# Addon-mapleCUx_Raspi-3V3-UART-CC2530-V03.net
KiCad netlist of a schematic drawn in EAGLE
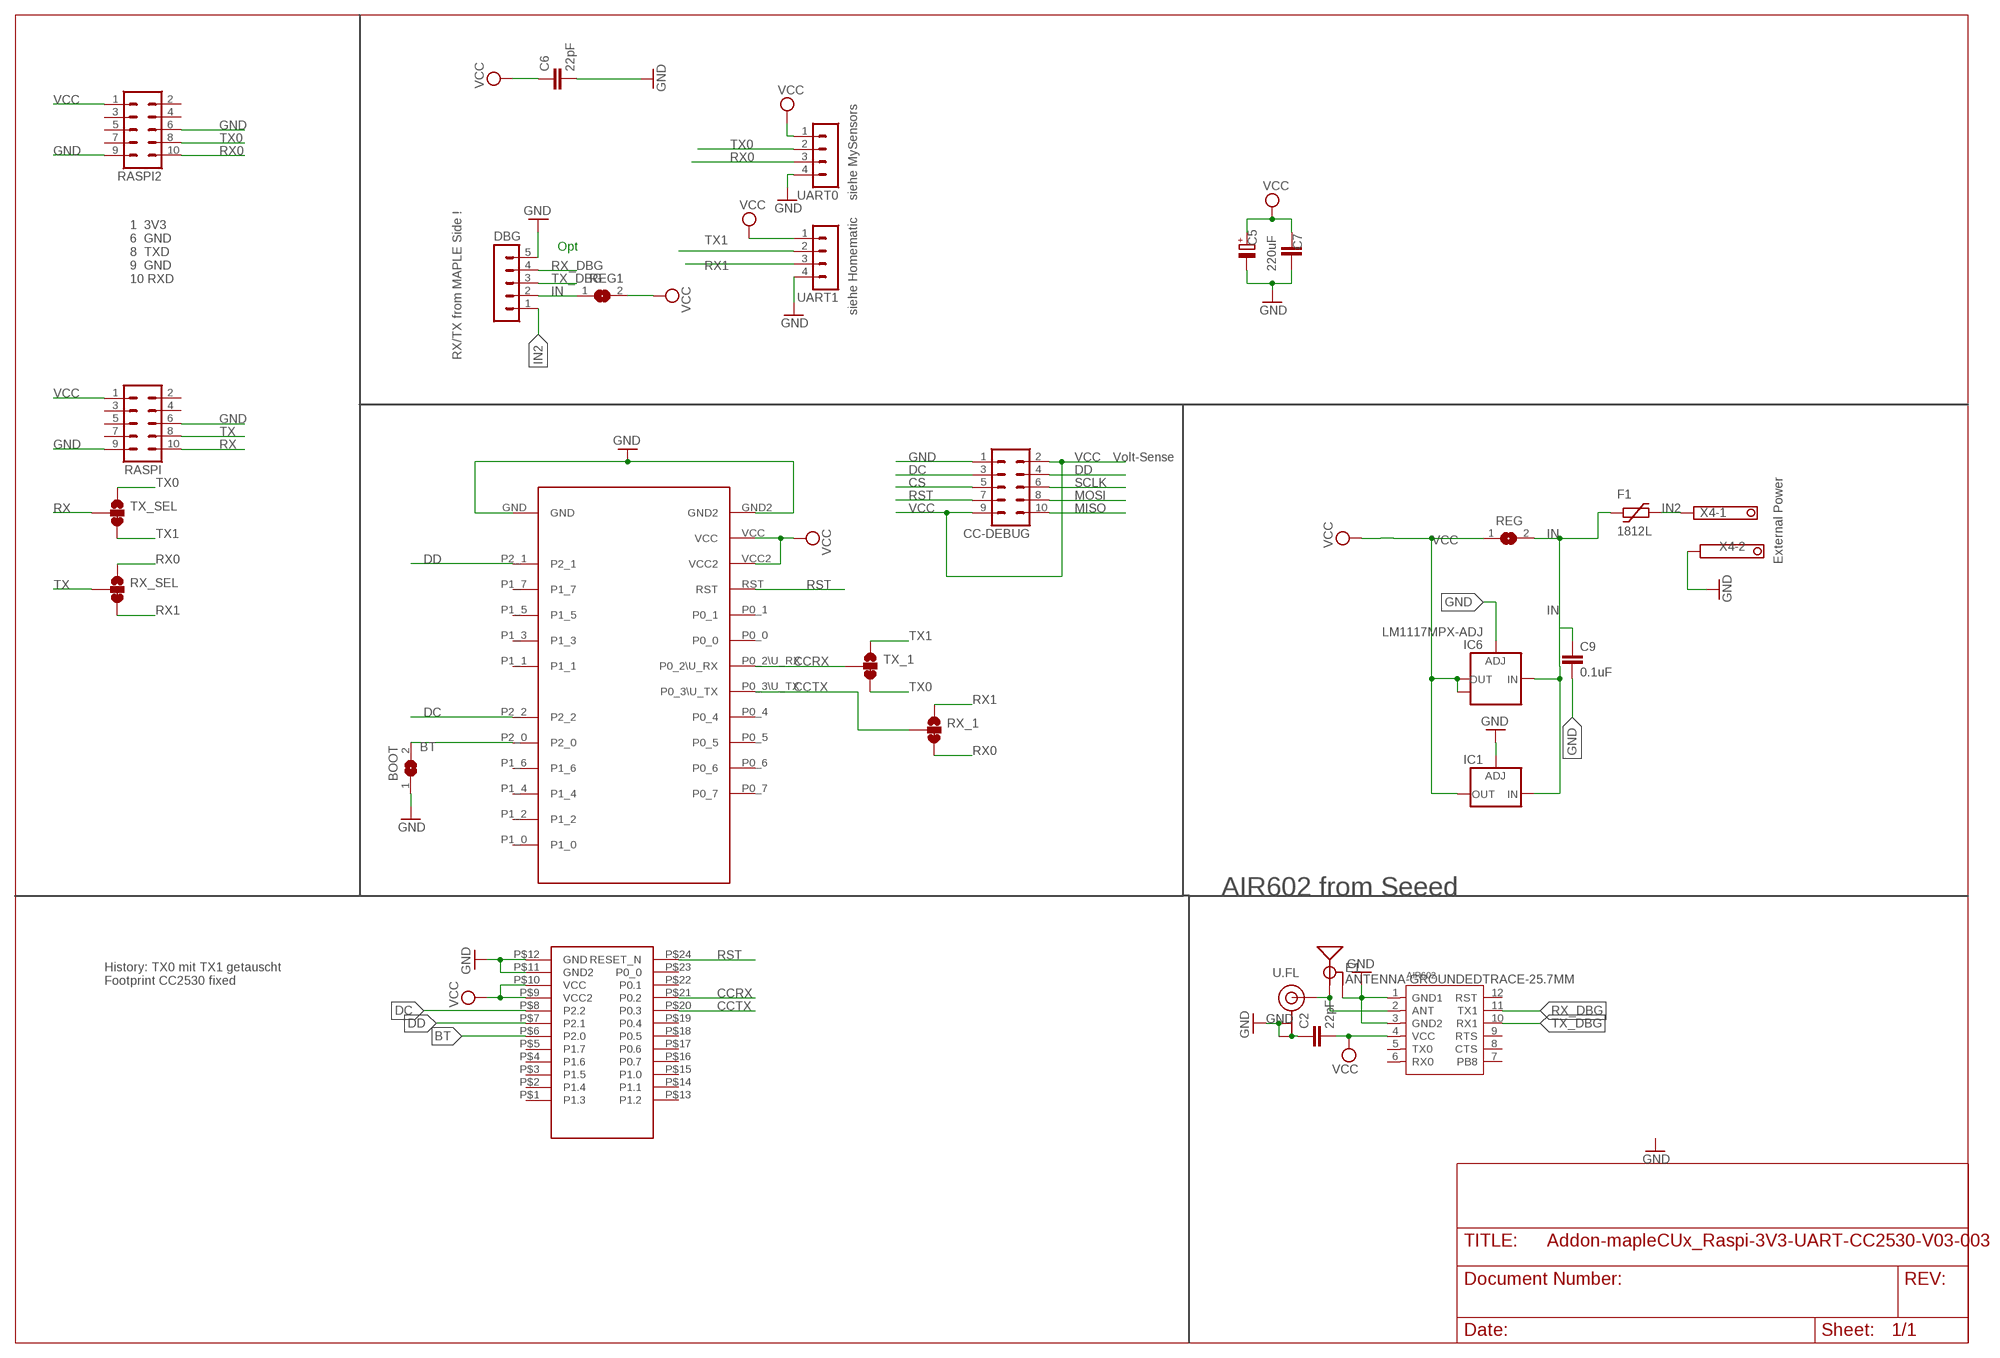
[diagram p0: schematic, sheet 1]

(export (version "E")
  (design (tool "Eeschema 10.0.6"))
  (components
    (comp (ref "AIR602")
      (value "AIR602")
      (footprint "eagle-import:MODULE12P-2.0-10X12MM")
      (libsource (lib "eagle-import") (part "AIR602"))
    )
    (comp (ref "BOOT")
      (value "SJ")
      (footprint "eagle-import:SJ")
      (libsource (lib "eagle-import") (part "SJ"))
    )
    (comp (ref "C2")
      (value "22pF")
      (footprint "eagle-import:C0805")
      (libsource (lib "eagle-import") (part "C-EUC0805"))
    )
    (comp (ref "C5")
      (value "220uF")
      (footprint "eagle-import:E5-8,5")
      (libsource (lib "eagle-import") (part "CPOL-EUE5-8.5"))
    )
    (comp (ref "C6")
      (value "22pF")
      (footprint "eagle-import:C0805")
      (libsource (lib "eagle-import") (part "rcl_334_C-EUC0805"))
    )
    (comp (ref "C7")
      (value "C-EUC1812")
      (footprint "eagle-import:C1812")
      (libsource (lib "eagle-import") (part "rcl_334_C-EUC1812"))
    )
    (comp (ref "C9")
      (value "0.1uF")
      (footprint "eagle-import:C1206")
      (libsource (lib "eagle-import") (part "rcl_334_C-EUC1206"))
    )
    (comp (ref "CC-DEBUG")
      (value "MA05-2")
      (footprint "eagle-import:MA05-2")
      (libsource (lib "eagle-import") (part "MA05-2"))
    )
    (comp (ref "DBG")
      (value "MA05-1")
      (footprint "eagle-import:MA05-1")
      (libsource (lib "eagle-import") (part "MA05-1"))
    )
    (comp (ref "E1")
      (value "ANTENNA-GROUNDEDTRACE-25.7MM")
      (footprint "eagle-import:TRACE_ANTENNA_2.4GHZ_25.7MM")
      (libsource (lib "eagle-import") (part "ANTENNA-GROUNDEDTRACE-25.7MM"))
    )
    (comp (ref "F1")
      (value "1812L")
      (footprint "eagle-import:1812L")
      (libsource (lib "eagle-import") (part "1812L"))
    )
    (comp (ref "IC1")
      (value "LD117ADT50TR")
      (footprint "eagle-import:DPACK")
      (libsource (lib "eagle-import") (part "LD117A?DT50TR"))
    )
    (comp (ref "IC6")
      (value "LM1117MPX-ADJ")
      (footprint "eagle-import:SOT223")
      (libsource (lib "eagle-import") (part "LM1117MPX-ADJ"))
    )
    (comp (ref "RASPI")
      (value "MA05-2")
      (footprint "eagle-import:MA05-2")
      (libsource (lib "eagle-import") (part "MA05-2"))
    )
    (comp (ref "RASPI2")
      (value "MA05-2")
      (footprint "eagle-import:MA05-2")
      (libsource (lib "eagle-import") (part "MA05-2"))
    )
    (comp (ref "REG") (value "SJ") (footprint "eagle-import:SJ") (libsource (lib "eagle-import") (part "SJ")))
    (comp (ref "REG1")
      (value "SJ")
      (footprint "eagle-import:SJ")
      (libsource (lib "eagle-import") (part "SJ"))
    )
    (comp (ref "RX_1")
      (value "JUMPER-SMT_3_1-NC_TRACE_SILK")
      (footprint "eagle-import:SMT-JUMPER_3_1-NC_TRACE_SILK")
      (libsource (lib "eagle-import") (part "JUMPER-SMT_3_1-NC_TRACE_SILK"))
    )
    (comp (ref "RX_SEL")
      (value "JUMPER-SMT_3_1-NC_TRACE_SILK")
      (footprint "eagle-import:SMT-JUMPER_3_1-NC_TRACE_SILK")
      (libsource (lib "eagle-import") (part "JUMPER-SMT_3_1-NC_TRACE_SILK"))
    )
    (comp (ref "TX_1")
      (value "JUMPER-SMT_3_1-NC_TRACE_SILK")
      (footprint "eagle-import:SMT-JUMPER_3_1-NC_TRACE_SILK")
      (libsource (lib "eagle-import") (part "JUMPER-SMT_3_1-NC_TRACE_SILK"))
    )
    (comp (ref "TX_SEL")
      (value "JUMPER-SMT_3_1-NC_TRACE_SILK")
      (footprint "eagle-import:SMT-JUMPER_3_1-NC_TRACE_SILK")
      (libsource (lib "eagle-import") (part "JUMPER-SMT_3_1-NC_TRACE_SILK"))
    )
    (comp (ref "U$1")
      (value "CC2530CC2530PA")
      (footprint "eagle-import:CC2530PA")
      (libsource (lib "eagle-import") (part "CC2530CC2530PA"))
    )
    (comp (ref "U$3")
      (value "CC2530_MODULE")
      (footprint "eagle-import:CC2530_DIL")
      (libsource (lib "eagle-import") (part "CC2530_MODULE"))
    )
    (comp (ref "U.FL")
      (value "U.FL")
      (footprint "eagle-import:U.FL")
      (libsource (lib "eagle-import") (part "U.FL"))
    )
    (comp (ref "UART0")
      (value "MA04-1")
      (footprint "eagle-import:MA04-1")
      (libsource (lib "eagle-import") (part "MA04-1"))
    )
    (comp (ref "UART1")
      (value "MA04-1")
      (footprint "eagle-import:MA04-1")
      (libsource (lib "eagle-import") (part "MA04-1"))
    )
    (comp (ref "X4")
      (value "1751248")
      (footprint "eagle-import:1751248")
      (libsource (lib "eagle-import") (part "1751248"))
    )
  )
  (nets
    (net (code "1") (name "/CCRX") (class "Default")
      (node (ref "TX_1") (pin "2") (pinfunction "2_2") (pintype "passive"))
      (node (ref "U$1") (pin "P$21") (pinfunction "P0.2_P$21") (pintype "bidirectional"))
      (node (ref "U$3") (pin "P0_2\\U_RX") (pinfunction "P0_2\\U_RX_P0_2\\U_RX") (pintype "bidirectional"))
    )
    (net (code "2") (name "/CCTX") (class "Default")
      (node (ref "RX_1") (pin "2") (pinfunction "2_2") (pintype "passive"))
      (node (ref "U$1") (pin "P$20") (pinfunction "P0.3_P$20") (pintype "bidirectional"))
      (node (ref "U$3") (pin "P0_3\\U_TX") (pinfunction "P0_3\\U_TX_P0_3\\U_TX") (pintype "bidirectional"))
    )
    (net (code "3") (name "/CS") (class "Default")
      (node (ref "CC-DEBUG") (pin "5") (pinfunction "5_5") (pintype "passive"))
    )
    (net (code "4") (name "/IN") (class "Default")
      (node (ref "C9") (pin "1") (pinfunction "1_1") (pintype "passive"))
      (node (ref "DBG") (pin "2") (pinfunction "2_2") (pintype "passive"))
      (node (ref "F1") (pin "P$1") (pinfunction "1_P$1") (pintype "passive"))
      (node (ref "IC1") (pin "3") (pinfunction "IN_3") (pintype "input"))
      (node (ref "IC6") (pin "3") (pinfunction "IN_3") (pintype "input"))
      (node (ref "REG") (pin "2") (pinfunction "2_2") (pintype "passive"))
      (node (ref "REG1") (pin "1") (pinfunction "1_1") (pintype "passive"))
    )
    (net (code "5") (name "/MISO") (class "Default")
      (node (ref "CC-DEBUG") (pin "10") (pinfunction "10_10") (pintype "passive"))
    )
    (net (code "6") (name "/MOSI") (class "Default")
      (node (ref "CC-DEBUG") (pin "8") (pinfunction "8_8") (pintype "passive"))
    )
    (net (code "7") (name "/RST") (class "Default")
      (node (ref "CC-DEBUG") (pin "7") (pinfunction "7_7") (pintype "passive"))
      (node (ref "U$1") (pin "P$24") (pinfunction "RESET_N_P$24") (pintype "bidirectional"))
      (node (ref "U$3") (pin "RST") (pinfunction "RST_RST") (pintype "bidirectional"))
    )
    (net (code "8") (name "/RX") (class "Default")
      (node (ref "RASPI") (pin "10") (pinfunction "10_10") (pintype "passive"))
      (node (ref "TX_SEL") (pin "2") (pinfunction "2_2") (pintype "passive"))
    )
    (net (code "9") (name "/RX0") (class "Default")
      (node (ref "RASPI2") (pin "10") (pinfunction "10_10") (pintype "passive"))
      (node (ref "RX_1") (pin "3") (pinfunction "3_3") (pintype "passive"))
      (node (ref "RX_SEL") (pin "1") (pinfunction "1_1") (pintype "passive"))
      (node (ref "UART0") (pin "3") (pinfunction "3_3") (pintype "passive"))
    )
    (net (code "10") (name "/RX1") (class "Default")
      (node (ref "RX_1") (pin "1") (pinfunction "1_1") (pintype "passive"))
      (node (ref "RX_SEL") (pin "3") (pinfunction "3_3") (pintype "passive"))
      (node (ref "UART1") (pin "3") (pinfunction "3_3") (pintype "passive"))
    )
    (net (code "11") (name "/SCLK") (class "Default")
      (node (ref "CC-DEBUG") (pin "6") (pinfunction "6_6") (pintype "passive"))
    )
    (net (code "12") (name "/TX") (class "Default")
      (node (ref "RASPI") (pin "8") (pinfunction "8_8") (pintype "passive"))
      (node (ref "RX_SEL") (pin "2") (pinfunction "2_2") (pintype "passive"))
    )
    (net (code "13") (name "/TX0") (class "Default")
      (node (ref "RASPI2") (pin "8") (pinfunction "8_8") (pintype "passive"))
      (node (ref "TX_1") (pin "3") (pinfunction "3_3") (pintype "passive"))
      (node (ref "TX_SEL") (pin "1") (pinfunction "1_1") (pintype "passive"))
      (node (ref "UART0") (pin "2") (pinfunction "2_2") (pintype "passive"))
    )
    (net (code "14") (name "/TX1") (class "Default")
      (node (ref "TX_1") (pin "1") (pinfunction "1_1") (pintype "passive"))
      (node (ref "TX_SEL") (pin "3") (pinfunction "3_3") (pintype "passive"))
      (node (ref "UART1") (pin "2") (pinfunction "2_2") (pintype "passive"))
    )
    (net (code "15") (name "BT") (class "Default")
      (node (ref "BOOT") (pin "2") (pinfunction "2_2") (pintype "passive"))
      (node (ref "U$1") (pin "P$6") (pinfunction "P2.0_P$6") (pintype "bidirectional"))
      (node (ref "U$3") (pin "P2_0") (pinfunction "P2_0_P2_0") (pintype "bidirectional"))
    )
    (net (code "16") (name "DC") (class "Default")
      (node (ref "CC-DEBUG") (pin "3") (pinfunction "3_3") (pintype "passive"))
      (node (ref "U$1") (pin "P$8") (pinfunction "P2.2_P$8") (pintype "bidirectional"))
      (node (ref "U$3") (pin "P2_2") (pinfunction "P2_2_P2_2") (pintype "bidirectional"))
    )
    (net (code "17") (name "DD") (class "Default")
      (node (ref "CC-DEBUG") (pin "4") (pinfunction "4_4") (pintype "passive"))
      (node (ref "U$1") (pin "P$7") (pinfunction "P2.1_P$7") (pintype "bidirectional"))
      (node (ref "U$3") (pin "P2_1") (pinfunction "P2_1_P2_1") (pintype "bidirectional"))
    )
    (net (code "18") (name "GND") (class "Default")
      (node (ref "AIR602") (pin "1") (pinfunction "GND1_1") (pintype "bidirectional"))
      (node (ref "AIR602") (pin "3") (pinfunction "GND2_3") (pintype "bidirectional"))
      (node (ref "BOOT") (pin "1") (pinfunction "1_1") (pintype "passive"))
      (node (ref "C2") (pin "1") (pinfunction "1_1") (pintype "passive"))
      (node (ref "C5") (pin "-") (pinfunction "-_-") (pintype "passive"))
      (node (ref "C6") (pin "2") (pinfunction "2_2") (pintype "passive"))
      (node (ref "C7") (pin "1") (pinfunction "1_1") (pintype "passive"))
      (node (ref "C9") (pin "2") (pinfunction "2_2") (pintype "passive"))
      (node (ref "CC-DEBUG") (pin "1") (pinfunction "1_1") (pintype "passive"))
      (node (ref "DBG") (pin "5") (pinfunction "5_5") (pintype "passive"))
      (node (ref "E1") (pin "GND") (pinfunction "GND_GND") (pintype "bidirectional"))
      (node (ref "E1") (pin "GND2") (pinfunction "GND_GND2") (pintype "bidirectional"))
      (node (ref "IC1") (pin "1") (pinfunction "ADJ_1") (pintype "input"))
      (node (ref "IC6") (pin "1") (pinfunction "ADJ_1") (pintype "input"))
      (node (ref "RASPI") (pin "6") (pinfunction "6_6") (pintype "passive"))
      (node (ref "RASPI") (pin "9") (pinfunction "9_9") (pintype "passive"))
      (node (ref "RASPI2") (pin "6") (pinfunction "6_6") (pintype "passive"))
      (node (ref "RASPI2") (pin "9") (pinfunction "9_9") (pintype "passive"))
      (node (ref "U$1") (pin "P$11") (pinfunction "GND2_P$11") (pintype "bidirectional"))
      (node (ref "U$1") (pin "P$12") (pinfunction "GND_P$12") (pintype "bidirectional"))
      (node (ref "U$3") (pin "GND") (pinfunction "GND_GND") (pintype "bidirectional"))
      (node (ref "U$3") (pin "GND2") (pinfunction "GND2_GND2") (pintype "bidirectional"))
      (node (ref "U.FL") (pin "1") (pinfunction "GND_1") (pintype "bidirectional"))
      (node (ref "U.FL") (pin "2") (pinfunction "GND_2") (pintype "bidirectional"))
      (node (ref "UART0") (pin "4") (pinfunction "4_4") (pintype "passive"))
      (node (ref "UART1") (pin "4") (pinfunction "4_4") (pintype "passive"))
      (node (ref "X4") (pin "2") (pinfunction "K_2") (pintype "passive"))
    )
    (net (code "19") (name "IN2") (class "Default")
      (node (ref "DBG") (pin "1") (pinfunction "1_1") (pintype "passive"))
      (node (ref "F1") (pin "P$2") (pinfunction "2_P$2") (pintype "passive"))
      (node (ref "X4") (pin "1") (pinfunction "K_1") (pintype "passive"))
    )
    (net (code "20") (name "Net-(AIR602-ANT)") (class "Default")
      (node (ref "AIR602") (pin "2") (pinfunction "ANT_2") (pintype "bidirectional"))
      (node (ref "E1") (pin "ANT") (pinfunction "SIGNAL_ANT") (pintype "bidirectional"))
      (node (ref "U.FL") (pin "FEED") (pinfunction "SIGNAL_FEED") (pintype "bidirectional"))
    )
    (net (code "21") (name "RX_DBG") (class "Default")
      (node (ref "AIR602") (pin "11") (pinfunction "TX1_11") (pintype "bidirectional"))
      (node (ref "DBG") (pin "4") (pinfunction "4_4") (pintype "passive"))
    )
    (net (code "22") (name "TX_DBG") (class "Default")
      (node (ref "AIR602") (pin "10") (pinfunction "RX1_10") (pintype "bidirectional"))
      (node (ref "DBG") (pin "3") (pinfunction "3_3") (pintype "passive"))
    )
    (net (code "23") (name "VCC") (class "Default")
      (node (ref "AIR602") (pin "4") (pinfunction "VCC_4") (pintype "bidirectional"))
      (node (ref "C2") (pin "2") (pinfunction "2_2") (pintype "passive"))
      (node (ref "C5") (pin "+") (pinfunction "+_+") (pintype "passive"))
      (node (ref "C6") (pin "1") (pinfunction "1_1") (pintype "passive"))
      (node (ref "C7") (pin "2") (pinfunction "2_2") (pintype "passive"))
      (node (ref "CC-DEBUG") (pin "2") (pinfunction "2_2") (pintype "passive"))
      (node (ref "CC-DEBUG") (pin "9") (pinfunction "9_9") (pintype "passive"))
      (node (ref "IC1") (pin "4") (pinfunction "OUT_4") (pintype "passive"))
      (node (ref "IC6") (pin "2") (pinfunction "OUT_2") (pintype "passive"))
      (node (ref "IC6") (pin "TAB") (pinfunction "OUT1_TAB") (pintype "passive"))
      (node (ref "RASPI") (pin "1") (pinfunction "1_1") (pintype "passive"))
      (node (ref "RASPI2") (pin "1") (pinfunction "1_1") (pintype "passive"))
      (node (ref "REG") (pin "1") (pinfunction "1_1") (pintype "passive"))
      (node (ref "REG1") (pin "2") (pinfunction "2_2") (pintype "passive"))
      (node (ref "U$1") (pin "P$10") (pinfunction "VCC_P$10") (pintype "bidirectional"))
      (node (ref "U$1") (pin "P$9") (pinfunction "VCC2_P$9") (pintype "bidirectional"))
      (node (ref "U$3") (pin "VCC") (pinfunction "VCC_VCC") (pintype "bidirectional"))
      (node (ref "U$3") (pin "VCC2") (pinfunction "VCC2_VCC2") (pintype "bidirectional"))
      (node (ref "UART0") (pin "1") (pinfunction "1_1") (pintype "passive"))
      (node (ref "UART1") (pin "1") (pinfunction "1_1") (pintype "passive"))
    )
    (net (code "24") (name "unconnected-(AIR602-CTS-Pad8)") (class "Default")
      (node (ref "AIR602") (pin "8") (pinfunction "CTS_8") (pintype "bidirectional"))
    )
    (net (code "25") (name "unconnected-(AIR602-PB8-Pad7)") (class "Default")
      (node (ref "AIR602") (pin "7") (pinfunction "PB8_7") (pintype "bidirectional"))
    )
    (net (code "26") (name "unconnected-(AIR602-RST-Pad12)") (class "Default")
      (node (ref "AIR602") (pin "12") (pinfunction "RST_12") (pintype "bidirectional"))
    )
    (net (code "27") (name "unconnected-(AIR602-RTS-Pad9)") (class "Default")
      (node (ref "AIR602") (pin "9") (pinfunction "RTS_9") (pintype "bidirectional"))
    )
    (net (code "28") (name "unconnected-(AIR602-RX0-Pad6)") (class "Default")
      (node (ref "AIR602") (pin "6") (pinfunction "RX0_6") (pintype "bidirectional"))
    )
    (net (code "29") (name "unconnected-(AIR602-TX0-Pad5)") (class "Default")
      (node (ref "AIR602") (pin "5") (pinfunction "TX0_5") (pintype "bidirectional"))
    )
    (net (code "30") (name "unconnected-(RASPI-Pad2)") (class "Default")
      (node (ref "RASPI") (pin "2") (pinfunction "2_2") (pintype "passive"))
    )
    (net (code "31") (name "unconnected-(RASPI-Pad3)") (class "Default")
      (node (ref "RASPI") (pin "3") (pinfunction "3_3") (pintype "passive"))
    )
    (net (code "32") (name "unconnected-(RASPI-Pad4)") (class "Default")
      (node (ref "RASPI") (pin "4") (pinfunction "4_4") (pintype "passive"))
    )
    (net (code "33") (name "unconnected-(RASPI-Pad5)") (class "Default")
      (node (ref "RASPI") (pin "5") (pinfunction "5_5") (pintype "passive"))
    )
    (net (code "34") (name "unconnected-(RASPI-Pad7)") (class "Default")
      (node (ref "RASPI") (pin "7") (pinfunction "7_7") (pintype "passive"))
    )
    (net (code "35") (name "unconnected-(RASPI2-Pad2)") (class "Default")
      (node (ref "RASPI2") (pin "2") (pinfunction "2_2") (pintype "passive"))
    )
    (net (code "36") (name "unconnected-(RASPI2-Pad3)") (class "Default")
      (node (ref "RASPI2") (pin "3") (pinfunction "3_3") (pintype "passive"))
    )
    (net (code "37") (name "unconnected-(RASPI2-Pad4)") (class "Default")
      (node (ref "RASPI2") (pin "4") (pinfunction "4_4") (pintype "passive"))
    )
    (net (code "38") (name "unconnected-(RASPI2-Pad5)") (class "Default")
      (node (ref "RASPI2") (pin "5") (pinfunction "5_5") (pintype "passive"))
    )
    (net (code "39") (name "unconnected-(RASPI2-Pad7)") (class "Default")
      (node (ref "RASPI2") (pin "7") (pinfunction "7_7") (pintype "passive"))
    )
    (net (code "40") (name "unconnected-(U$1-P0.1-PadP$22)") (class "Default")
      (node (ref "U$1") (pin "P$22") (pinfunction "P0.1_P$22") (pintype "bidirectional"))
    )
    (net (code "41") (name "unconnected-(U$1-P0.4-PadP$19)") (class "Default")
      (node (ref "U$1") (pin "P$19") (pinfunction "P0.4_P$19") (pintype "bidirectional"))
    )
    (net (code "42") (name "unconnected-(U$1-P0.5-PadP$18)") (class "Default")
      (node (ref "U$1") (pin "P$18") (pinfunction "P0.5_P$18") (pintype "bidirectional"))
    )
    (net (code "43") (name "unconnected-(U$1-P0.6-PadP$17)") (class "Default")
      (node (ref "U$1") (pin "P$17") (pinfunction "P0.6_P$17") (pintype "bidirectional"))
    )
    (net (code "44") (name "unconnected-(U$1-P0.7-PadP$16)") (class "Default")
      (node (ref "U$1") (pin "P$16") (pinfunction "P0.7_P$16") (pintype "bidirectional"))
    )
    (net (code "45") (name "unconnected-(U$1-P0_0-PadP$23)") (class "Default")
      (node (ref "U$1") (pin "P$23") (pinfunction "P0_0_P$23") (pintype "bidirectional"))
    )
    (net (code "46") (name "unconnected-(U$1-P1.0-PadP$15)") (class "Default")
      (node (ref "U$1") (pin "P$15") (pinfunction "P1.0_P$15") (pintype "bidirectional"))
    )
    (net (code "47") (name "unconnected-(U$1-P1.1-PadP$14)") (class "Default")
      (node (ref "U$1") (pin "P$14") (pinfunction "P1.1_P$14") (pintype "bidirectional"))
    )
    (net (code "48") (name "unconnected-(U$1-P1.2-PadP$13)") (class "Default")
      (node (ref "U$1") (pin "P$13") (pinfunction "P1.2_P$13") (pintype "bidirectional"))
    )
    (net (code "49") (name "unconnected-(U$1-P1.3-PadP$1)") (class "Default")
      (node (ref "U$1") (pin "P$1") (pinfunction "P1.3_P$1") (pintype "bidirectional"))
    )
    (net (code "50") (name "unconnected-(U$1-P1.4-PadP$2)") (class "Default")
      (node (ref "U$1") (pin "P$2") (pinfunction "P1.4_P$2") (pintype "bidirectional"))
    )
    (net (code "51") (name "unconnected-(U$1-P1.5-PadP$3)") (class "Default")
      (node (ref "U$1") (pin "P$3") (pinfunction "P1.5_P$3") (pintype "bidirectional"))
    )
    (net (code "52") (name "unconnected-(U$1-P1.6-PadP$4)") (class "Default")
      (node (ref "U$1") (pin "P$4") (pinfunction "P1.6_P$4") (pintype "bidirectional"))
    )
    (net (code "53") (name "unconnected-(U$1-P1.7-PadP$5)") (class "Default")
      (node (ref "U$1") (pin "P$5") (pinfunction "P1.7_P$5") (pintype "bidirectional"))
    )
    (net (code "54") (name "unconnected-(U$3-PadP0_0)") (class "Default")
      (node (ref "U$3") (pin "P0_0") (pinfunction "P0_0_P0_0") (pintype "bidirectional"))
    )
    (net (code "55") (name "unconnected-(U$3-PadP0_1)") (class "Default")
      (node (ref "U$3") (pin "P0_1") (pinfunction "P0_1_P0_1") (pintype "bidirectional"))
    )
    (net (code "56") (name "unconnected-(U$3-PadP0_4)") (class "Default")
      (node (ref "U$3") (pin "P0_4") (pinfunction "P0_4_P0_4") (pintype "bidirectional"))
    )
    (net (code "57") (name "unconnected-(U$3-PadP0_5)") (class "Default")
      (node (ref "U$3") (pin "P0_5") (pinfunction "P0_5_P0_5") (pintype "bidirectional"))
    )
    (net (code "58") (name "unconnected-(U$3-PadP0_6)") (class "Default")
      (node (ref "U$3") (pin "P0_6") (pinfunction "P0_6_P0_6") (pintype "bidirectional"))
    )
    (net (code "59") (name "unconnected-(U$3-PadP0_7)") (class "Default")
      (node (ref "U$3") (pin "P0_7") (pinfunction "P0_7_P0_7") (pintype "bidirectional"))
    )
    (net (code "60") (name "unconnected-(U$3-PadP1_0)") (class "Default")
      (node (ref "U$3") (pin "P1_0") (pinfunction "P1_0_P1_0") (pintype "bidirectional"))
    )
    (net (code "61") (name "unconnected-(U$3-PadP1_1)") (class "Default")
      (node (ref "U$3") (pin "P1_1") (pinfunction "P1_1_P1_1") (pintype "bidirectional"))
    )
    (net (code "62") (name "unconnected-(U$3-PadP1_2)") (class "Default")
      (node (ref "U$3") (pin "P1_2") (pinfunction "P1_2_P1_2") (pintype "bidirectional"))
    )
    (net (code "63") (name "unconnected-(U$3-PadP1_3)") (class "Default")
      (node (ref "U$3") (pin "P1_3") (pinfunction "P1_3_P1_3") (pintype "bidirectional"))
    )
    (net (code "64") (name "unconnected-(U$3-PadP1_4)") (class "Default")
      (node (ref "U$3") (pin "P1_4") (pinfunction "P1_4_P1_4") (pintype "bidirectional"))
    )
    (net (code "65") (name "unconnected-(U$3-PadP1_5)") (class "Default")
      (node (ref "U$3") (pin "P1_5") (pinfunction "P1_5_P1_5") (pintype "bidirectional"))
    )
    (net (code "66") (name "unconnected-(U$3-PadP1_6)") (class "Default")
      (node (ref "U$3") (pin "P1_6") (pinfunction "P1_6_P1_6") (pintype "bidirectional"))
    )
    (net (code "67") (name "unconnected-(U$3-PadP1_7)") (class "Default")
      (node (ref "U$3") (pin "P1_7") (pinfunction "P1_7_P1_7") (pintype "bidirectional"))
    )
  )
)
